# Ikea_Molgan.net
KiCad netlist of a schematic drawn in EAGLE
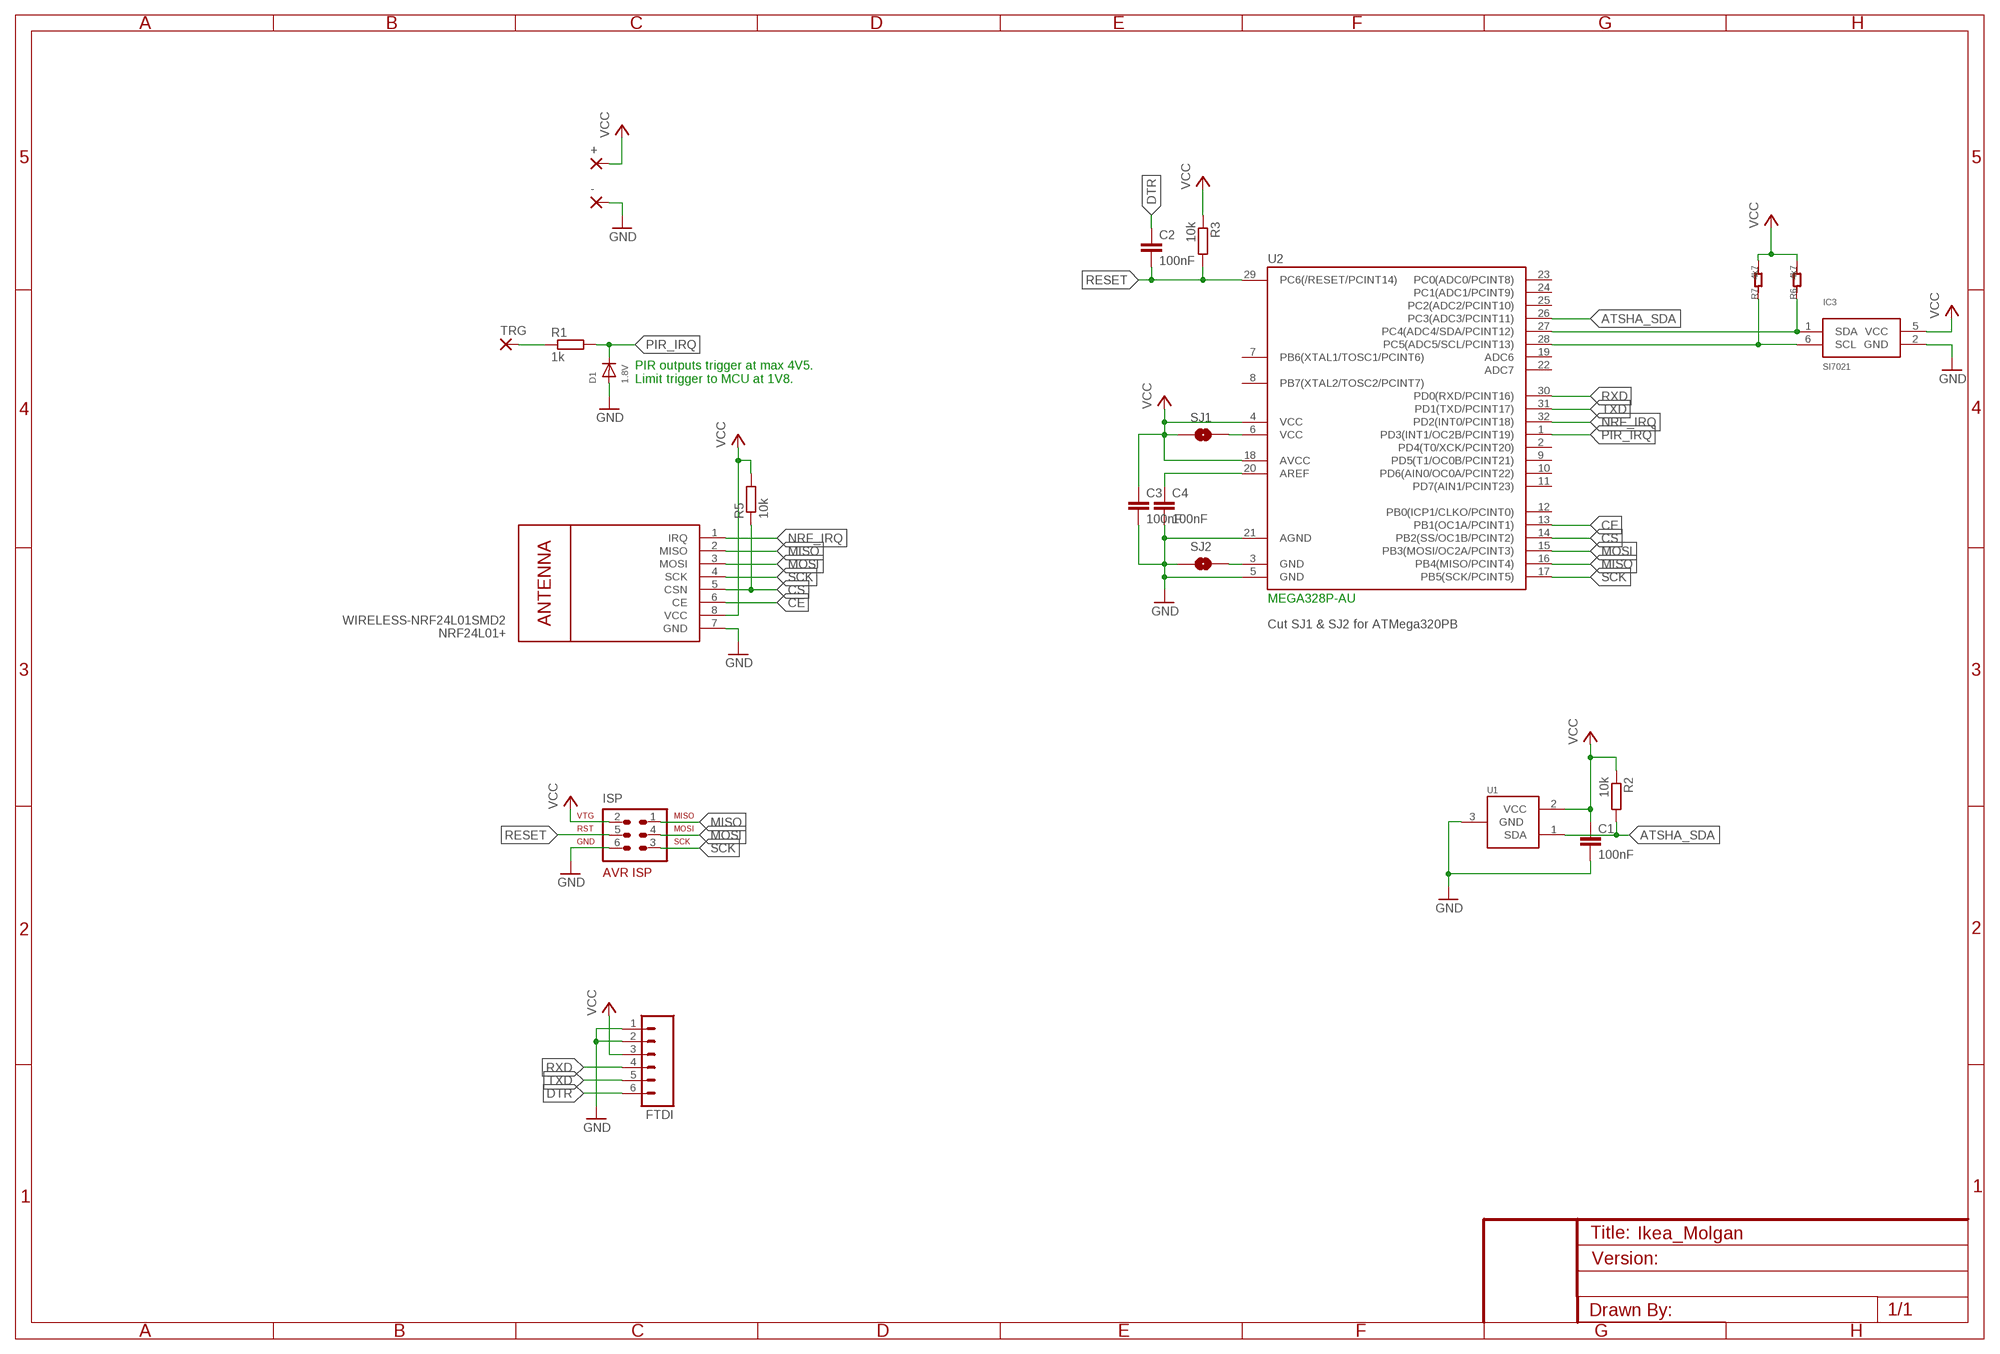
[diagram p0: schematic, sheet 1]

(export (version "E")
  (design (tool "Eeschema 10.0.6"))
  (components
    (comp (ref "+")
      (value "WIREPADSMD2,54-5,08")
      (footprint "eagle-import:SMD2,54-5,08")
      (libsource (lib "eagle-import") (part "WIREPADSMD2,54-5,08"))
    )
    (comp (ref "-")
      (value "WIREPADSMD2,54-5,08")
      (footprint "eagle-import:SMD2,54-5,08")
      (libsource (lib "eagle-import") (part "WIREPADSMD2,54-5,08"))
    )
    (comp (ref "C1")
      (value "100nF")
      (footprint "eagle-import:C0805")
      (libsource (lib "eagle-import") (part "C-EUC0805"))
    )
    (comp (ref "C2")
      (value "100nF")
      (footprint "eagle-import:C0805")
      (libsource (lib "eagle-import") (part "C-EUC0805"))
    )
    (comp (ref "C3")
      (value "100nF")
      (footprint "eagle-import:C0805")
      (libsource (lib "eagle-import") (part "C-EUC0805"))
    )
    (comp (ref "C4")
      (value "100nF")
      (footprint "eagle-import:C0805")
      (libsource (lib "eagle-import") (part "C-EUC0805"))
    )
    (comp (ref "D1")
      (value "1.8V")
      (footprint "eagle-import:SOD-123")
      (libsource (lib "eagle-import") (part "DIODESOD-123"))
    )
    (comp (ref "FTDI")
      (value "M06SIP")
      (footprint "eagle-import:1X06")
      (libsource (lib "eagle-import") (part "M06SIP"))
    )
    (comp (ref "IC3")
      (value "SI7021")
      (footprint "eagle-import:DFN6")
      (libsource (lib "eagle-import") (part "SI7021"))
    )
    (comp (ref "ISP")
      (value "AVR-ISP-6")
      (footprint "eagle-import:AVR-ISP-6")
      (libsource (lib "eagle-import") (part "AVR-ISP-6"))
    )
    (comp (ref "NRF24L01+")
      (value "WIRELESS-NRF24L01SMD2")
      (footprint "eagle-import:WIRELESS-NRF24L01-SMD-2")
      (libsource (lib "eagle-import") (part "WIRELESS-NRF24L01SMD2"))
    )
    (comp (ref "R1")
      (value "1k")
      (footprint "eagle-import:R0805")
      (libsource (lib "eagle-import") (part "R-EU_R0805"))
    )
    (comp (ref "R2")
      (value "10k")
      (footprint "eagle-import:R0805")
      (libsource (lib "eagle-import") (part "R-EU_R0805"))
    )
    (comp (ref "R3")
      (value "10k")
      (footprint "eagle-import:R0805")
      (libsource (lib "eagle-import") (part "R-EU_R0805"))
    )
    (comp (ref "R5")
      (value "10k")
      (footprint "eagle-import:R0805")
      (libsource (lib "eagle-import") (part "R-EU_R0805"))
    )
    (comp (ref "R6")
      (value "4k7")
      (footprint "eagle-import:R0402")
      (libsource (lib "eagle-import") (part "R-0402"))
    )
    (comp (ref "R7")
      (value "4k7")
      (footprint "eagle-import:R0402")
      (libsource (lib "eagle-import") (part "R-0402"))
    )
    (comp (ref "SJ1")
      (value "SOLDERJUMPERTRACE")
      (footprint "eagle-import:SJ_2S-TRACE")
      (libsource (lib "eagle-import") (part "SOLDERJUMPERTRACE"))
    )
    (comp (ref "SJ2")
      (value "SOLDERJUMPERTRACE")
      (footprint "eagle-import:SJ_2S-TRACE")
      (libsource (lib "eagle-import") (part "SOLDERJUMPERTRACE"))
    )
    (comp (ref "TRG")
      (value "WIREPADSMD2,54-5,08")
      (footprint "eagle-import:SMD2,54-5,08")
      (libsource (lib "eagle-import") (part "WIREPADSMD2,54-5,08"))
    )
    (comp (ref "U1")
      (value "IC_ATSHA204A_CRYPT")
      (footprint "eagle-import:SOT23-3")
      (libsource (lib "eagle-import") (part "IC_ATSHA204A_CRYPT"))
    )
    (comp (ref "U2")
      (value "MEGA328P-AU")
      (footprint "eagle-import:TQFP32-08")
      (libsource (lib "eagle-import") (part "MEGA48/88/168-AU"))
    )
  )
  (nets
    (net (code "1") (name "ATSHA_SDA") (class "Default")
      (node (ref "R2") (pin "2") (pinfunction "2_2") (pintype "passive"))
      (node (ref "U1") (pin "1") (pinfunction "SDA_1") (pintype "bidirectional"))
      (node (ref "U2") (pin "26") (pinfunction "PC3(ADC3/PCINT11)_26") (pintype "bidirectional"))
    )
    (net (code "2") (name "CE") (class "Default")
      (node (ref "NRF24L01+") (pin "6") (pinfunction "CE_6") (pintype "bidirectional"))
      (node (ref "U2") (pin "13") (pinfunction "PB1(OC1A/PCINT1)_13") (pintype "bidirectional"))
    )
    (net (code "3") (name "CS") (class "Default")
      (node (ref "NRF24L01+") (pin "5") (pinfunction "CSN_5") (pintype "bidirectional"))
      (node (ref "R5") (pin "1") (pinfunction "1_1") (pintype "passive"))
      (node (ref "U2") (pin "14") (pinfunction "PB2(SS/OC1B/PCINT2)_14") (pintype "bidirectional"))
    )
    (net (code "4") (name "DTR") (class "Default")
      (node (ref "C2") (pin "1") (pinfunction "1_1") (pintype "passive"))
      (node (ref "FTDI") (pin "6") (pinfunction "6_6") (pintype "passive"))
    )
    (net (code "5") (name "GND") (class "Default")
      (node (ref "-") (pin "1") (pinfunction "P_1") (pintype "passive"))
      (node (ref "C1") (pin "2") (pinfunction "2_2") (pintype "passive"))
      (node (ref "C3") (pin "2") (pinfunction "2_2") (pintype "passive"))
      (node (ref "C4") (pin "2") (pinfunction "2_2") (pintype "passive"))
      (node (ref "D1") (pin "A") (pinfunction "A_A") (pintype "passive"))
      (node (ref "FTDI") (pin "1") (pinfunction "1_1") (pintype "passive"))
      (node (ref "FTDI") (pin "2") (pinfunction "2_2") (pintype "passive"))
      (node (ref "IC3") (pin "2") (pinfunction "GND_2") (pintype "bidirectional"))
      (node (ref "ISP") (pin "6") (pinfunction "6_6") (pintype "passive"))
      (node (ref "NRF24L01+") (pin "7") (pinfunction "GND_7") (pintype "power_in"))
      (node (ref "SJ2") (pin "1") (pinfunction "1_1") (pintype "passive"))
      (node (ref "U1") (pin "3") (pinfunction "GND_3") (pintype "bidirectional"))
      (node (ref "U2") (pin "21") (pinfunction "AGND_21") (pintype "power_in"))
      (node (ref "U2") (pin "5") (pinfunction "GND_5") (pintype "power_in"))
    )
    (net (code "6") (name "MISO") (class "Default")
      (node (ref "ISP") (pin "1") (pinfunction "1_1") (pintype "passive"))
      (node (ref "NRF24L01+") (pin "2") (pinfunction "MISO_2") (pintype "bidirectional"))
      (node (ref "U2") (pin "16") (pinfunction "PB4(MISO/PCINT4)_16") (pintype "bidirectional"))
    )
    (net (code "7") (name "MOSI") (class "Default")
      (node (ref "ISP") (pin "4") (pinfunction "4_4") (pintype "passive"))
      (node (ref "NRF24L01+") (pin "3") (pinfunction "MOSI_3") (pintype "bidirectional"))
      (node (ref "U2") (pin "15") (pinfunction "PB3(MOSI/OC2A/PCINT3)_15") (pintype "bidirectional"))
    )
    (net (code "8") (name "NRF_IRQ") (class "Default")
      (node (ref "NRF24L01+") (pin "1") (pinfunction "IRQ_1") (pintype "bidirectional"))
      (node (ref "U2") (pin "32") (pinfunction "PD2(INT0/PCINT18)_32") (pintype "bidirectional"))
    )
    (net (code "9") (name "Net-(IC3-SCL)") (class "Default")
      (node (ref "IC3") (pin "6") (pinfunction "SCL_6") (pintype "bidirectional"))
      (node (ref "R7") (pin "1") (pinfunction "1_1") (pintype "bidirectional"))
      (node (ref "U2") (pin "28") (pinfunction "PC5(ADC5/SCL/PCINT13)_28") (pintype "bidirectional"))
    )
    (net (code "10") (name "Net-(IC3-SDA)") (class "Default")
      (node (ref "IC3") (pin "1") (pinfunction "SDA_1") (pintype "bidirectional"))
      (node (ref "R6") (pin "1") (pinfunction "1_1") (pintype "bidirectional"))
      (node (ref "U2") (pin "27") (pinfunction "PC4(ADC4/SDA/PCINT12)_27") (pintype "bidirectional"))
    )
    (net (code "11") (name "Net-(SJ1-Pad2)") (class "Default")
      (node (ref "SJ1") (pin "2") (pinfunction "2_2") (pintype "passive"))
      (node (ref "U2") (pin "6") (pinfunction "VCC_6") (pintype "power_in"))
    )
    (net (code "12") (name "Net-(SJ2-Pad2)") (class "Default")
      (node (ref "SJ2") (pin "2") (pinfunction "2_2") (pintype "passive"))
      (node (ref "U2") (pin "3") (pinfunction "GND_3") (pintype "power_in"))
    )
    (net (code "13") (name "Net-(TRG-P)") (class "Default")
      (node (ref "R1") (pin "1") (pinfunction "1_1") (pintype "passive"))
      (node (ref "TRG") (pin "1") (pinfunction "P_1") (pintype "passive"))
    )
    (net (code "14") (name "Net-(U2-AREF)") (class "Default")
      (node (ref "C4") (pin "1") (pinfunction "1_1") (pintype "passive"))
      (node (ref "U2") (pin "20") (pinfunction "AREF_20") (pintype "passive"))
    )
    (net (code "15") (name "PIR_IRQ") (class "Default")
      (node (ref "D1") (pin "C") (pinfunction "C_C") (pintype "passive"))
      (node (ref "R1") (pin "2") (pinfunction "2_2") (pintype "passive"))
      (node (ref "U2") (pin "1") (pinfunction "PD3(INT1/OC2B/PCINT19)_1") (pintype "bidirectional"))
    )
    (net (code "16") (name "RESET") (class "Default")
      (node (ref "C2") (pin "2") (pinfunction "2_2") (pintype "passive"))
      (node (ref "ISP") (pin "5") (pinfunction "5_5") (pintype "passive"))
      (node (ref "R3") (pin "2") (pinfunction "2_2") (pintype "passive"))
      (node (ref "U2") (pin "29") (pinfunction "PC6(/RESET/PCINT14)_29") (pintype "bidirectional"))
    )
    (net (code "17") (name "RXD") (class "Default")
      (node (ref "FTDI") (pin "4") (pinfunction "4_4") (pintype "passive"))
      (node (ref "U2") (pin "30") (pinfunction "PD0(RXD/PCINT16)_30") (pintype "bidirectional"))
    )
    (net (code "18") (name "SCK") (class "Default")
      (node (ref "ISP") (pin "3") (pinfunction "3_3") (pintype "passive"))
      (node (ref "NRF24L01+") (pin "4") (pinfunction "SCK_4") (pintype "bidirectional"))
      (node (ref "U2") (pin "17") (pinfunction "PB5(SCK/PCINT5)_17") (pintype "bidirectional"))
    )
    (net (code "19") (name "TXD") (class "Default")
      (node (ref "FTDI") (pin "5") (pinfunction "5_5") (pintype "passive"))
      (node (ref "U2") (pin "31") (pinfunction "PD1(TXD/PCINT17)_31") (pintype "bidirectional"))
    )
    (net (code "20") (name "VCC") (class "Default")
      (node (ref "+") (pin "1") (pinfunction "P_1") (pintype "passive"))
      (node (ref "C1") (pin "1") (pinfunction "1_1") (pintype "passive"))
      (node (ref "C3") (pin "1") (pinfunction "1_1") (pintype "passive"))
      (node (ref "FTDI") (pin "3") (pinfunction "3_3") (pintype "passive"))
      (node (ref "IC3") (pin "5") (pinfunction "VCC_5") (pintype "bidirectional"))
      (node (ref "ISP") (pin "2") (pinfunction "2_2") (pintype "passive"))
      (node (ref "NRF24L01+") (pin "8") (pinfunction "VCC_8") (pintype "power_in"))
      (node (ref "R2") (pin "1") (pinfunction "1_1") (pintype "passive"))
      (node (ref "R3") (pin "1") (pinfunction "1_1") (pintype "passive"))
      (node (ref "R5") (pin "2") (pinfunction "2_2") (pintype "passive"))
      (node (ref "R6") (pin "2") (pinfunction "2_2") (pintype "bidirectional"))
      (node (ref "R7") (pin "2") (pinfunction "2_2") (pintype "bidirectional"))
      (node (ref "SJ1") (pin "1") (pinfunction "1_1") (pintype "passive"))
      (node (ref "U1") (pin "2") (pinfunction "VCC_2") (pintype "bidirectional"))
      (node (ref "U2") (pin "18") (pinfunction "AVCC_18") (pintype "passive"))
      (node (ref "U2") (pin "4") (pinfunction "VCC_4") (pintype "power_in"))
    )
    (net (code "21") (name "unconnected-(U2-ADC6-Pad19)") (class "Default")
      (node (ref "U2") (pin "19") (pinfunction "ADC6_19") (pintype "passive"))
    )
    (net (code "22") (name "unconnected-(U2-ADC7-Pad22)") (class "Default")
      (node (ref "U2") (pin "22") (pinfunction "ADC7_22") (pintype "passive"))
    )
    (net (code "23") (name "unconnected-(U2-PB0(ICP1{slash}CLKO{slash}PCINT0)-Pad12)") (class "Default")
      (node (ref "U2") (pin "12") (pinfunction "PB0(ICP1/CLKO/PCINT0)_12") (pintype "bidirectional"))
    )
    (net (code "24") (name "unconnected-(U2-PB6(XTAL1{slash}TOSC1{slash}PCINT6)-Pad7)") (class "Default")
      (node (ref "U2") (pin "7") (pinfunction "PB6(XTAL1/TOSC1/PCINT6)_7") (pintype "bidirectional"))
    )
    (net (code "25") (name "unconnected-(U2-PB7(XTAL2{slash}TOSC2{slash}PCINT7)-Pad8)") (class "Default")
      (node (ref "U2") (pin "8") (pinfunction "PB7(XTAL2/TOSC2/PCINT7)_8") (pintype "bidirectional"))
    )
    (net (code "26") (name "unconnected-(U2-PC0(ADC0{slash}PCINT8)-Pad23)") (class "Default")
      (node (ref "U2") (pin "23") (pinfunction "PC0(ADC0/PCINT8)_23") (pintype "bidirectional"))
    )
    (net (code "27") (name "unconnected-(U2-PC1(ADC1{slash}PCINT9)-Pad24)") (class "Default")
      (node (ref "U2") (pin "24") (pinfunction "PC1(ADC1/PCINT9)_24") (pintype "bidirectional"))
    )
    (net (code "28") (name "unconnected-(U2-PC2(ADC2{slash}PCINT10)-Pad25)") (class "Default")
      (node (ref "U2") (pin "25") (pinfunction "PC2(ADC2/PCINT10)_25") (pintype "bidirectional"))
    )
    (net (code "29") (name "unconnected-(U2-PD4(T0{slash}XCK{slash}PCINT20)-Pad2)") (class "Default")
      (node (ref "U2") (pin "2") (pinfunction "PD4(T0/XCK/PCINT20)_2") (pintype "bidirectional"))
    )
    (net (code "30") (name "unconnected-(U2-PD5(T1{slash}OC0B{slash}PCINT21)-Pad9)") (class "Default")
      (node (ref "U2") (pin "9") (pinfunction "PD5(T1/OC0B/PCINT21)_9") (pintype "bidirectional"))
    )
    (net (code "31") (name "unconnected-(U2-PD6(AIN0{slash}OC0A{slash}PCINT22)-Pad10)") (class "Default")
      (node (ref "U2") (pin "10") (pinfunction "PD6(AIN0/OC0A/PCINT22)_10") (pintype "bidirectional"))
    )
    (net (code "32") (name "unconnected-(U2-PD7(AIN1{slash}PCINT23)-Pad11)") (class "Default")
      (node (ref "U2") (pin "11") (pinfunction "PD7(AIN1/PCINT23)_11") (pintype "bidirectional"))
    )
  )
)
